# 5vac-dc_reg.net
KiCad netlist of a schematic drawn in EAGLE
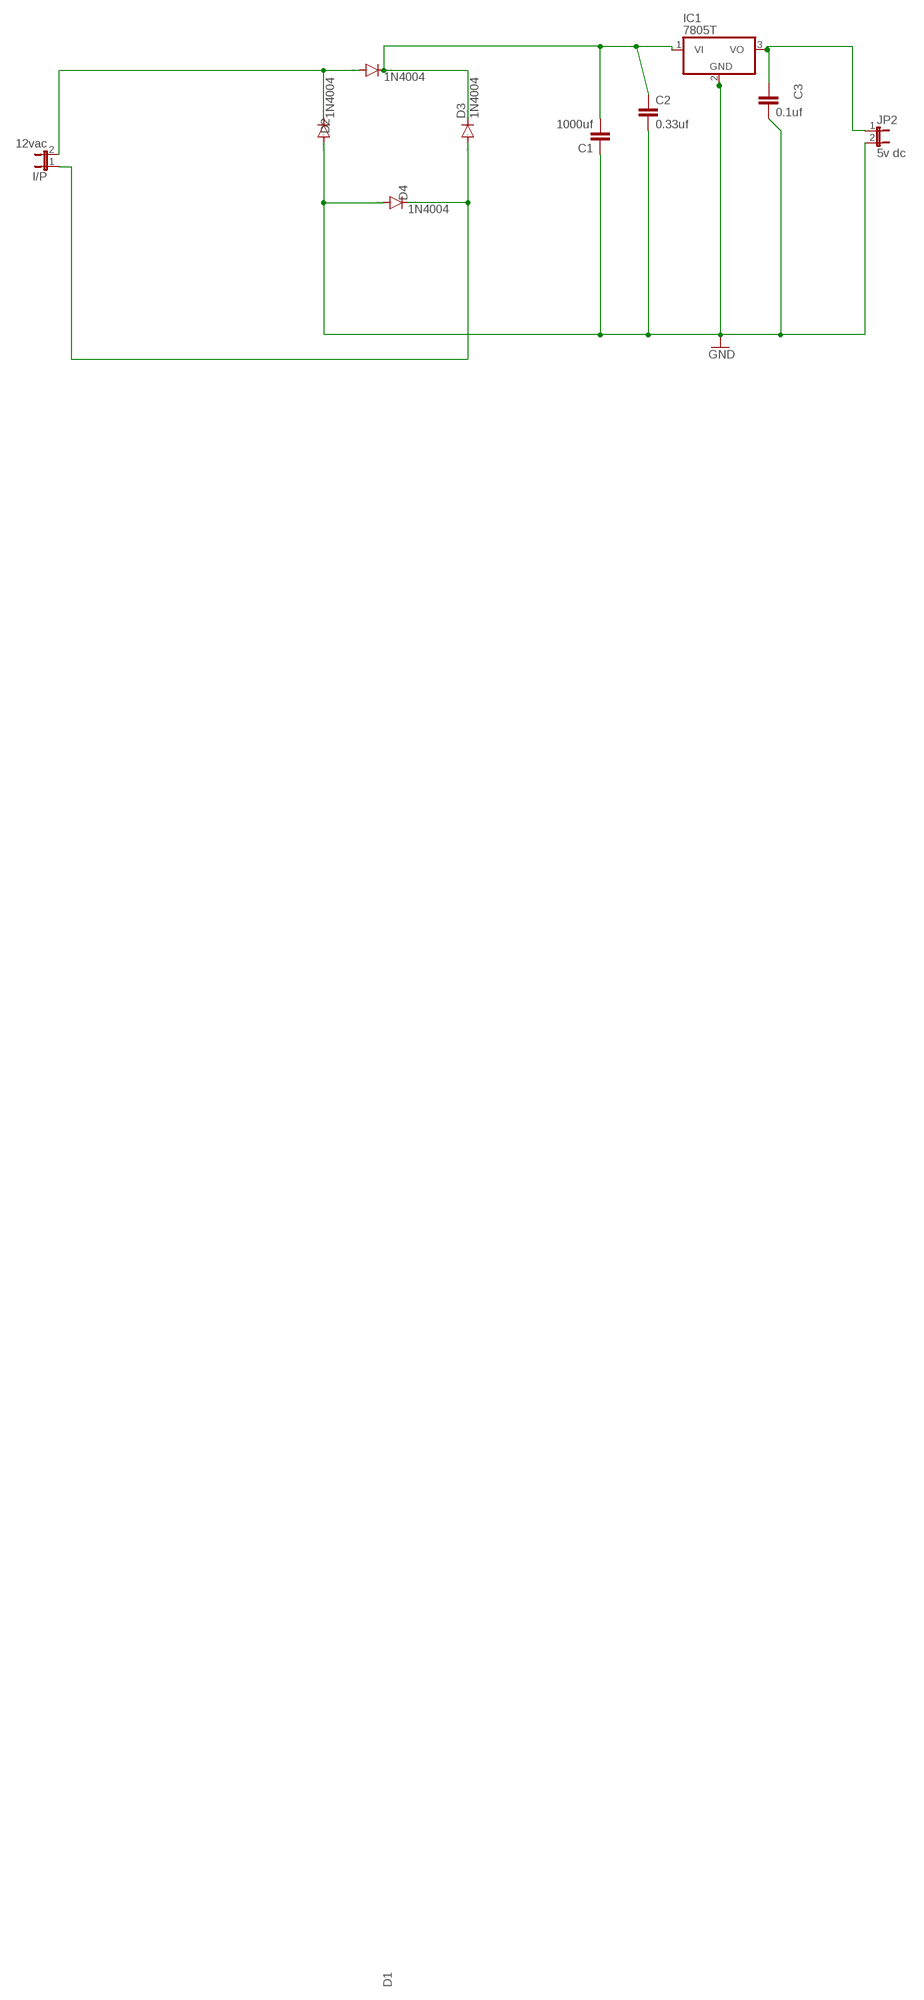
[diagram p0: schematic, sheet 1]

(export (version "E")
  (design (tool "Eeschema 10.0.6"))
  (components
    (comp (ref "C1")
      (value "1000uf")
      (footprint "eagle-import:C2.5-3")
      (libsource (lib "eagle-import") (part "C2,5-3"))
    )
    (comp (ref "C2")
      (value "0.33uf")
      (footprint "eagle-import:C2.5-3")
      (libsource (lib "eagle-import") (part "C2,5-3"))
    )
    (comp (ref "C3")
      (value "0.1uf")
      (footprint "eagle-import:C2.5-3")
      (libsource (lib "eagle-import") (part "C2,5-3"))
    )
    (comp (ref "D1")
      (value "1N4004")
      (footprint "eagle-import:DO41-10")
      (libsource (lib "eagle-import") (part "1N4004"))
    )
    (comp (ref "D2")
      (value "1N4004")
      (footprint "eagle-import:DO41-10")
      (libsource (lib "eagle-import") (part "1N4004"))
    )
    (comp (ref "D3")
      (value "1N4004")
      (footprint "eagle-import:DO41-10")
      (libsource (lib "eagle-import") (part "1N4004"))
    )
    (comp (ref "D4")
      (value "1N4004")
      (footprint "eagle-import:DO41-10")
      (libsource (lib "eagle-import") (part "1N4004"))
    )
    (comp (ref "I/P")
      (value "12vac")
      (footprint "eagle-import:JP1")
      (libsource (lib "eagle-import") (part "JP1E"))
    )
    (comp (ref "IC1")
      (value "7805T")
      (footprint "eagle-import:TO220H")
      (libsource (lib "eagle-import") (part "78T05"))
    )
    (comp (ref "JP2")
      (value "5v dc")
      (footprint "eagle-import:JP1")
      (libsource (lib "eagle-import") (part "JP1E"))
    )
  )
  (nets
    (net (code "1") (name "GND") (class "Default")
      (node (ref "C1") (pin "1") (pinfunction "1_1") (pintype "passive"))
      (node (ref "C2") (pin "2") (pinfunction "2_2") (pintype "passive"))
      (node (ref "C3") (pin "2") (pinfunction "2_2") (pintype "passive"))
      (node (ref "D2") (pin "A") (pinfunction "A_A") (pintype "passive"))
      (node (ref "D4") (pin "A") (pinfunction "A_A") (pintype "passive"))
      (node (ref "IC1") (pin "2") (pinfunction "GND_2") (pintype "passive"))
      (node (ref "JP2") (pin "2") (pinfunction "2_2") (pintype "passive"))
    )
    (net (code "2") (name "Net-(D1-PadA)") (class "Default")
      (node (ref "D1") (pin "A") (pinfunction "A_A") (pintype "passive"))
      (node (ref "D2") (pin "C") (pinfunction "C_C") (pintype "passive"))
      (node (ref "I/P") (pin "2") (pinfunction "2_2") (pintype "passive"))
    )
    (net (code "3") (name "Net-(D3-PadA)") (class "Default")
      (node (ref "D3") (pin "A") (pinfunction "A_A") (pintype "passive"))
      (node (ref "D4") (pin "C") (pinfunction "C_C") (pintype "passive"))
      (node (ref "I/P") (pin "1") (pinfunction "1_1") (pintype "passive"))
    )
    (net (code "4") (name "Net-(IC1-VI)") (class "Default")
      (node (ref "C1") (pin "2") (pinfunction "2_2") (pintype "passive"))
      (node (ref "C2") (pin "1") (pinfunction "1_1") (pintype "passive"))
      (node (ref "D1") (pin "C") (pinfunction "C_C") (pintype "passive"))
      (node (ref "D3") (pin "C") (pinfunction "C_C") (pintype "passive"))
      (node (ref "IC1") (pin "1") (pinfunction "VI_1") (pintype "input"))
    )
    (net (code "5") (name "Net-(IC1-VO)") (class "Default")
      (node (ref "C3") (pin "1") (pinfunction "1_1") (pintype "passive"))
      (node (ref "IC1") (pin "3") (pinfunction "VO_3") (pintype "passive"))
      (node (ref "JP2") (pin "1") (pinfunction "1_1") (pintype "passive"))
    )
  )
)
